# Pi_Servo_pHAT.net
KiCad netlist of a schematic drawn in EAGLE
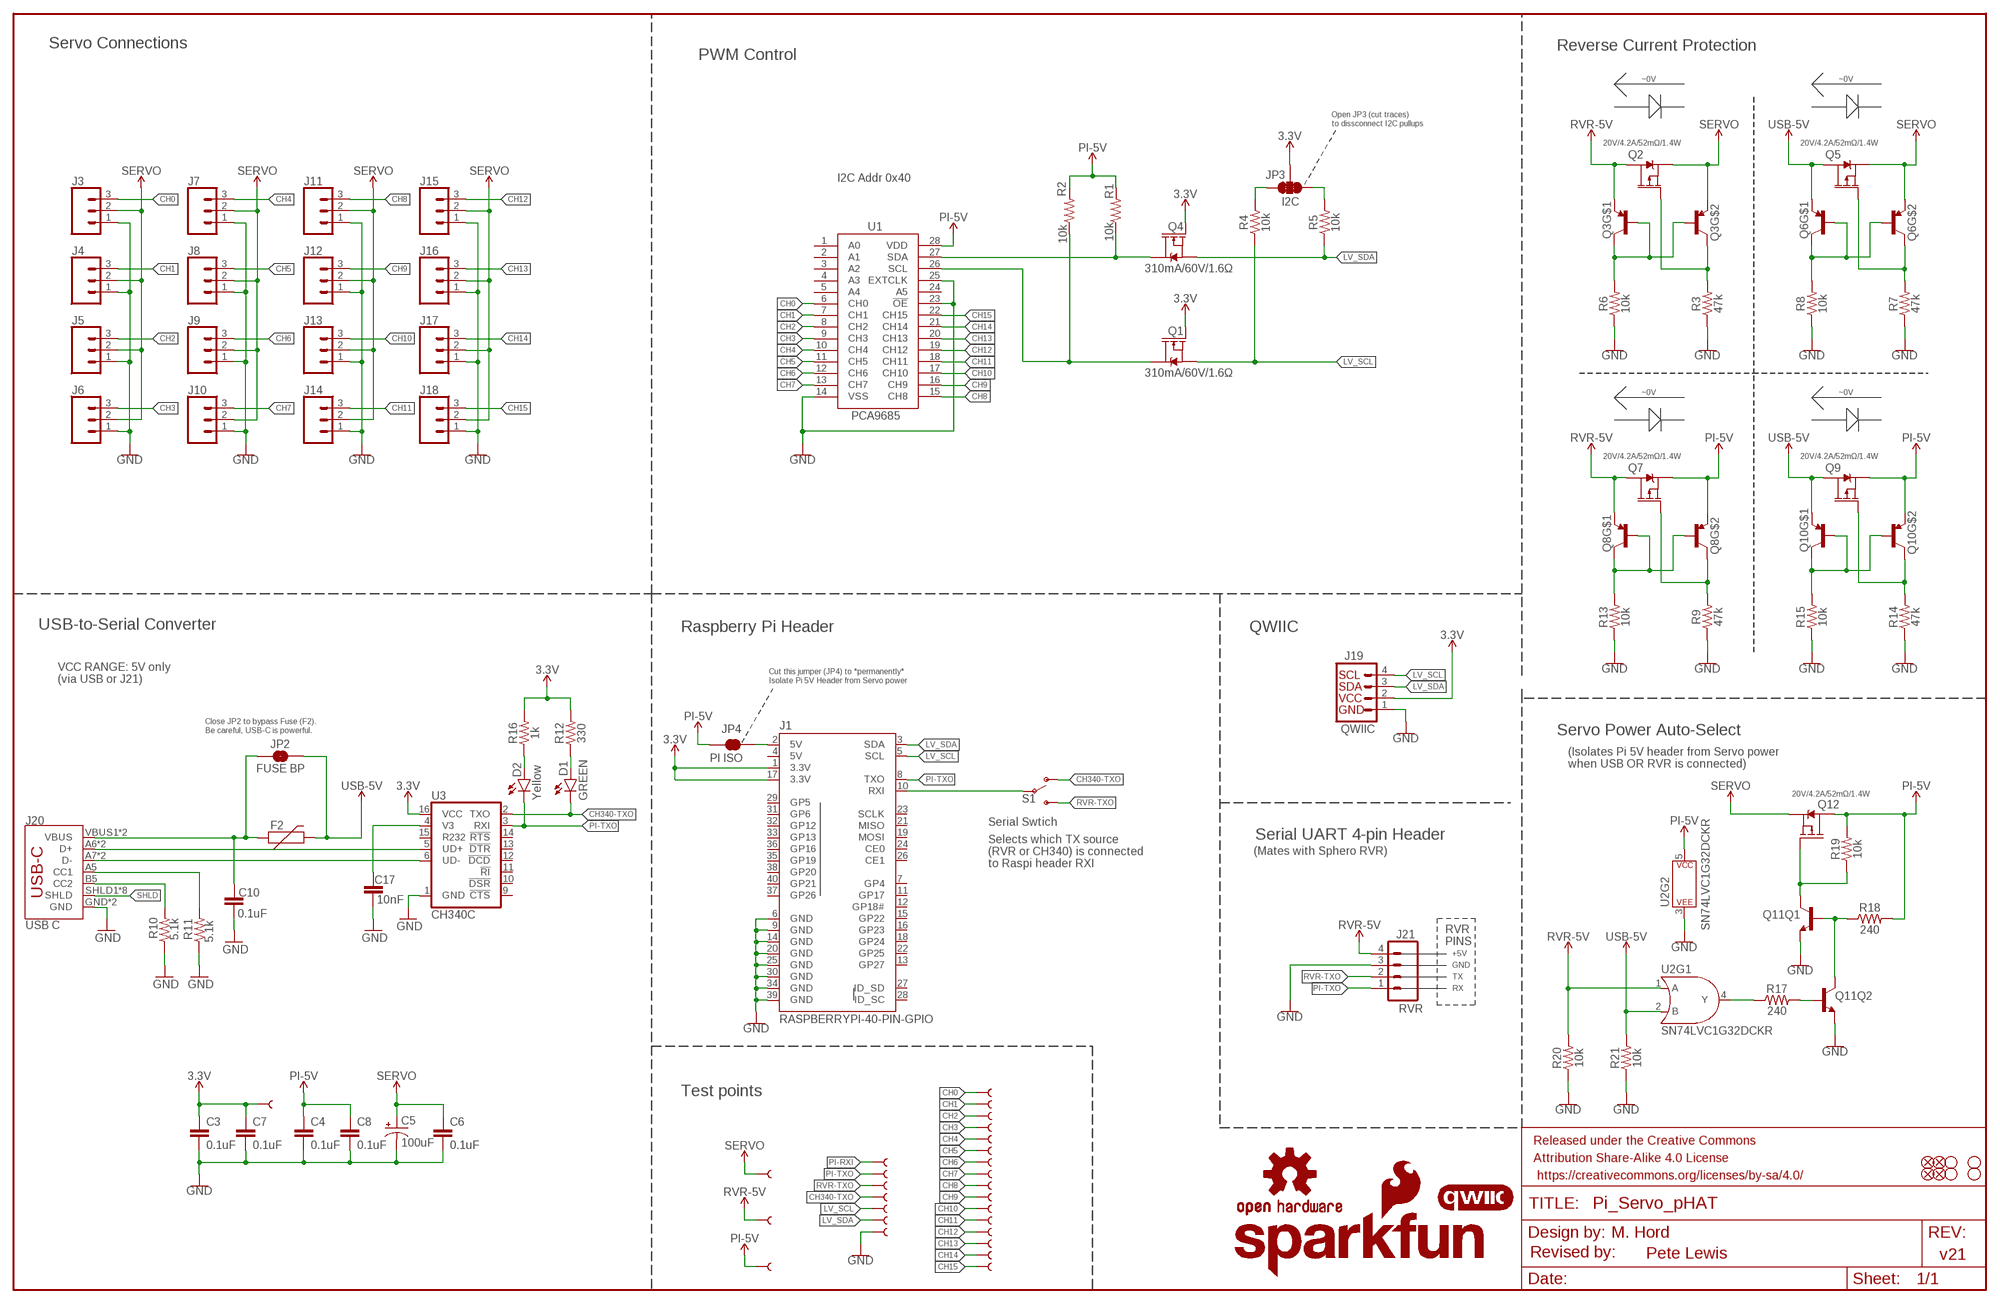
[diagram p0: schematic, sheet 1]

(export (version "E")
  (design (tool "Eeschema 10.0.6"))
  (components
    (comp (ref "C3")
      (value "0.1uF")
      (footprint "eagle-import:0603")
      (libsource (lib "eagle-import") (part "0.1UF-0603-25V-(+80/-20%)"))
    )
    (comp (ref "C4")
      (value "0.1uF")
      (footprint "eagle-import:0603")
      (libsource (lib "eagle-import") (part "0.1UF-0603-25V-(+80/-20%)"))
    )
    (comp (ref "C5")
      (value "100uF")
      (footprint "eagle-import:PANASONIC_D")
      (libsource (lib "eagle-import") (part "100UF-POLAR-25V-20%(ELEC)"))
    )
    (comp (ref "C6")
      (value "0.1uF")
      (footprint "eagle-import:0603")
      (libsource (lib "eagle-import") (part "0.1UF-0603-25V-(+80/-20%)"))
    )
    (comp (ref "C7")
      (value "0.1uF")
      (footprint "eagle-import:0603")
      (libsource (lib "eagle-import") (part "0.1UF-0603-25V-(+80/-20%)"))
    )
    (comp (ref "C8")
      (value "0.1uF")
      (footprint "eagle-import:0603")
      (libsource (lib "eagle-import") (part "0.1UF-0603-25V-(+80/-20%)"))
    )
    (comp (ref "C10")
      (value "0.1uF")
      (footprint "eagle-import:0603")
      (libsource (lib "eagle-import") (part "0.1UF-0603-25V-(+80/-20%)"))
    )
    (comp (ref "C17")
      (value "10nF")
      (footprint "eagle-import:0603")
      (libsource (lib "eagle-import") (part "10NF-0603-50V-10%"))
    )
    (comp (ref "D1")
      (value "GREEN")
      (footprint "eagle-import:LED-0603")
      (libsource (lib "eagle-import") (part "LED-GREEN0603"))
    )
    (comp (ref "D2")
      (value "Yellow")
      (footprint "eagle-import:LED-0603")
      (libsource (lib "eagle-import") (part "LED-YELLOW0603"))
    )
    (comp (ref "F2")
      (value "16V/2.5A(5A TRIP)")
      (footprint "eagle-import:1812")
      (libsource (lib "eagle-import") (part "PPTC_16V_2.5A"))
    )
    (comp (ref "FD1")
      (value "FIDUCIALUFIDUCIAL")
      (footprint "eagle-import:FIDUCIAL-MICRO")
      (libsource (lib "eagle-import") (part "FIDUCIALUFIDUCIAL"))
    )
    (comp (ref "FD2")
      (value "FIDUCIALUFIDUCIAL")
      (footprint "eagle-import:FIDUCIAL-MICRO")
      (libsource (lib "eagle-import") (part "FIDUCIALUFIDUCIAL"))
    )
    (comp (ref "FD3")
      (value "FIDUCIALUFIDUCIAL")
      (footprint "eagle-import:FIDUCIAL-MICRO")
      (libsource (lib "eagle-import") (part "FIDUCIALUFIDUCIAL"))
    )
    (comp (ref "FD4")
      (value "FIDUCIALUFIDUCIAL")
      (footprint "eagle-import:FIDUCIAL-MICRO")
      (libsource (lib "eagle-import") (part "FIDUCIALUFIDUCIAL"))
    )
    (comp (ref "FRAME2")
      (value "FRAME-LEDGER")
      (footprint "eagle-import:CREATIVE_COMMONS")
      (libsource (lib "eagle-import") (part "FRAME-LEDGER"))
    )
    (comp (ref "H1")
      (value "STAND-OFF")
      (footprint "eagle-import:STAND-OFF")
      (libsource (lib "eagle-import") (part "STAND-OFF"))
    )
    (comp (ref "H2")
      (value "STAND-OFF")
      (footprint "eagle-import:STAND-OFF")
      (libsource (lib "eagle-import") (part "STAND-OFF"))
    )
    (comp (ref "H3")
      (value "STAND-OFF")
      (footprint "eagle-import:STAND-OFF")
      (libsource (lib "eagle-import") (part "STAND-OFF"))
    )
    (comp (ref "H4")
      (value "STAND-OFF")
      (footprint "eagle-import:STAND-OFF")
      (libsource (lib "eagle-import") (part "STAND-OFF"))
    )
    (comp (ref "J1")
      (value "RASPBERRYPI-40-PIN-GPIO")
      (footprint "eagle-import:2X20")
      (libsource (lib "eagle-import") (part "RASPBERRYPI-40-PIN-GPIO_PTH_NO_SHROUD"))
    )
    (comp (ref "J3")
      (value "CONN_03")
      (footprint "eagle-import:1X03")
      (libsource (lib "eagle-import") (part "CONN_03"))
    )
    (comp (ref "J4")
      (value "CONN_03")
      (footprint "eagle-import:1X03")
      (libsource (lib "eagle-import") (part "CONN_03"))
    )
    (comp (ref "J5")
      (value "CONN_03")
      (footprint "eagle-import:1X03")
      (libsource (lib "eagle-import") (part "CONN_03"))
    )
    (comp (ref "J6")
      (value "CONN_03")
      (footprint "eagle-import:1X03")
      (libsource (lib "eagle-import") (part "CONN_03"))
    )
    (comp (ref "J7")
      (value "CONN_03")
      (footprint "eagle-import:1X03")
      (libsource (lib "eagle-import") (part "CONN_03"))
    )
    (comp (ref "J8")
      (value "CONN_03")
      (footprint "eagle-import:1X03")
      (libsource (lib "eagle-import") (part "CONN_03"))
    )
    (comp (ref "J9")
      (value "CONN_03")
      (footprint "eagle-import:1X03")
      (libsource (lib "eagle-import") (part "CONN_03"))
    )
    (comp (ref "J10")
      (value "CONN_03")
      (footprint "eagle-import:1X03")
      (libsource (lib "eagle-import") (part "CONN_03"))
    )
    (comp (ref "J11")
      (value "CONN_03")
      (footprint "eagle-import:1X03")
      (libsource (lib "eagle-import") (part "CONN_03"))
    )
    (comp (ref "J12")
      (value "CONN_03")
      (footprint "eagle-import:1X03")
      (libsource (lib "eagle-import") (part "CONN_03"))
    )
    (comp (ref "J13")
      (value "CONN_03")
      (footprint "eagle-import:1X03")
      (libsource (lib "eagle-import") (part "CONN_03"))
    )
    (comp (ref "J14")
      (value "CONN_03")
      (footprint "eagle-import:1X03")
      (libsource (lib "eagle-import") (part "CONN_03"))
    )
    (comp (ref "J15")
      (value "CONN_03")
      (footprint "eagle-import:1X03")
      (libsource (lib "eagle-import") (part "CONN_03"))
    )
    (comp (ref "J16")
      (value "CONN_03")
      (footprint "eagle-import:1X03")
      (libsource (lib "eagle-import") (part "CONN_03"))
    )
    (comp (ref "J17")
      (value "CONN_03")
      (footprint "eagle-import:1X03")
      (libsource (lib "eagle-import") (part "CONN_03"))
    )
    (comp (ref "J18")
      (value "CONN_03")
      (footprint "eagle-import:1X03")
      (libsource (lib "eagle-import") (part "CONN_03"))
    )
    (comp (ref "J19")
      (value "QWIIC")
      (footprint "eagle-import:JST04_1MM_RA")
      (libsource (lib "eagle-import") (part "QWIIC_CONNECTORJS-1MM"))
    )
    (comp (ref "J20")
      (value "USB C")
      (footprint "eagle-import:USB-C-16P")
      (libsource (lib "eagle-import") (part "USB_C16PIN"))
    )
    (comp (ref "J21")
      (value "RVR")
      (footprint "eagle-import:1X04_LOCK")
      (libsource (lib "eagle-import") (part "CONN_04LOCK"))
    )
    (comp (ref "JP2")
      (value "FUSE BP")
      (footprint "eagle-import:SMT-JUMPER_2_NO_SILK")
      (libsource (lib "eagle-import") (part "JUMPER-SMT_2_NO_SILK"))
    )
    (comp (ref "JP3")
      (value "I2C")
      (footprint "eagle-import:SMT-JUMPER_3_2-NC_TRACE_SILK")
      (libsource (lib "eagle-import") (part "JUMPER-SMT_3_2-NC_TRACE_SILK"))
    )
    (comp (ref "JP4")
      (value "PI ISO")
      (footprint "eagle-import:SMT-JUMPER_2_NC_TRACE_SILK")
      (libsource (lib "eagle-import") (part "JUMPER-SMT_2_NC_TRACE_SILK"))
    )
    (comp (ref "LOGO1")
      (value "SFE_LOGO_NAME_FLAME.1_INCH")
      (footprint "eagle-import:SFE_LOGO_NAME_FLAME_.1")
      (libsource (lib "eagle-import") (part "SFE_LOGO_NAME_FLAME.1_INCH"))
    )
    (comp (ref "LOGO2")
      (value "OSHW-LOGOS")
      (footprint "eagle-import:OSHW-LOGO-S")
      (libsource (lib "eagle-import") (part "OSHW-LOGOS"))
    )
    (comp (ref "Q1")
      (value "310mA/60V/1.6Ω")
      (footprint "eagle-import:SOT323")
      (libsource (lib "eagle-import") (part "MOSFET-NCH-2N7002PW"))
    )
    (comp (ref "Q2")
      (value "20V/4.2A/52mΩ/1.4W")
      (footprint "eagle-import:SOT23-3")
      (libsource (lib "eagle-import") (part "MOSFET_PCH-DMG2305UX-7"))
    )
    (comp (ref "Q3")
      (value "TRANS_PNP_DUALSOT-363")
      (footprint "eagle-import:SOT363_PHILIPS")
      (libsource (lib "eagle-import") (part "TRANS_PNP_DUALSOT-363"))
    )
    (comp (ref "Q4")
      (value "310mA/60V/1.6Ω")
      (footprint "eagle-import:SOT323")
      (libsource (lib "eagle-import") (part "MOSFET-NCH-2N7002PW"))
    )
    (comp (ref "Q5")
      (value "20V/4.2A/52mΩ/1.4W")
      (footprint "eagle-import:SOT23-3")
      (libsource (lib "eagle-import") (part "MOSFET_PCH-DMG2305UX-7"))
    )
    (comp (ref "Q6")
      (value "TRANS_PNP_DUALSOT-363")
      (footprint "eagle-import:SOT363_PHILIPS")
      (libsource (lib "eagle-import") (part "TRANS_PNP_DUALSOT-363"))
    )
    (comp (ref "Q7")
      (value "20V/4.2A/52mΩ/1.4W")
      (footprint "eagle-import:SOT23-3")
      (libsource (lib "eagle-import") (part "MOSFET_PCH-DMG2305UX-7"))
    )
    (comp (ref "Q8")
      (value "TRANS_PNP_DUALSOT-363")
      (footprint "eagle-import:SOT363_PHILIPS")
      (libsource (lib "eagle-import") (part "TRANS_PNP_DUALSOT-363"))
    )
    (comp (ref "Q9")
      (value "20V/4.2A/52mΩ/1.4W")
      (footprint "eagle-import:SOT23-3")
      (libsource (lib "eagle-import") (part "MOSFET_PCH-DMG2305UX-7"))
    )
    (comp (ref "Q10")
      (value "TRANS_PNP_DUALSOT-363")
      (footprint "eagle-import:SOT363_PHILIPS")
      (libsource (lib "eagle-import") (part "TRANS_PNP_DUALSOT-363"))
    )
    (comp (ref "Q11")
      (value "TRANS_NPN_DUAL-MBT3904DW1T1")
      (footprint "eagle-import:SC70-6")
      (libsource (lib "eagle-import") (part "TRANS_NPN_DUAL-MBT3904DW1T1"))
    )
    (comp (ref "Q12")
      (value "20V/4.2A/52mΩ/1.4W")
      (footprint "eagle-import:SOT23-3")
      (libsource (lib "eagle-import") (part "MOSFET_PCH-DMG2305UX-7"))
    )
    (comp (ref "R1")
      (value "10k")
      (footprint "eagle-import:0603")
      (libsource (lib "eagle-import") (part "10KOHM-0603-1/10W-1%"))
    )
    (comp (ref "R2")
      (value "10k")
      (footprint "eagle-import:0603")
      (libsource (lib "eagle-import") (part "10KOHM-0603-1/10W-1%"))
    )
    (comp (ref "R3")
      (value "47k")
      (footprint "eagle-import:0603")
      (libsource (lib "eagle-import") (part "47KOHM-0603-1/10W-1%"))
    )
    (comp (ref "R4")
      (value "10k")
      (footprint "eagle-import:0603")
      (libsource (lib "eagle-import") (part "10KOHM-0603-1/10W-1%"))
    )
    (comp (ref "R5")
      (value "10k")
      (footprint "eagle-import:0603")
      (libsource (lib "eagle-import") (part "10KOHM-0603-1/10W-1%"))
    )
    (comp (ref "R6")
      (value "10k")
      (footprint "eagle-import:0603")
      (libsource (lib "eagle-import") (part "10KOHM-0603-1/10W-1%"))
    )
    (comp (ref "R7")
      (value "47k")
      (footprint "eagle-import:0603")
      (libsource (lib "eagle-import") (part "47KOHM-0603-1/10W-1%"))
    )
    (comp (ref "R8")
      (value "10k")
      (footprint "eagle-import:0603")
      (libsource (lib "eagle-import") (part "10KOHM-0603-1/10W-1%"))
    )
    (comp (ref "R9")
      (value "47k")
      (footprint "eagle-import:0603")
      (libsource (lib "eagle-import") (part "47KOHM-0603-1/10W-1%"))
    )
    (comp (ref "R10")
      (value "5.1k")
      (footprint "eagle-import:0603")
      (libsource (lib "eagle-import") (part "5.1KOHM5.1KOHM-0603-1/10W-1%"))
    )
    (comp (ref "R11")
      (value "5.1k")
      (footprint "eagle-import:0603")
      (libsource (lib "eagle-import") (part "5.1KOHM5.1KOHM-0603-1/10W-1%"))
    )
    (comp (ref "R12")
      (value "330")
      (footprint "eagle-import:0603")
      (libsource (lib "eagle-import") (part "330OHM-0603-1/10W-1%"))
    )
    (comp (ref "R13")
      (value "10k")
      (footprint "eagle-import:0603")
      (libsource (lib "eagle-import") (part "10KOHM-0603-1/10W-1%"))
    )
    (comp (ref "R14")
      (value "47k")
      (footprint "eagle-import:0603")
      (libsource (lib "eagle-import") (part "47KOHM-0603-1/10W-1%"))
    )
    (comp (ref "R15")
      (value "10k")
      (footprint "eagle-import:0603")
      (libsource (lib "eagle-import") (part "10KOHM-0603-1/10W-1%"))
    )
    (comp (ref "R16")
      (value "1k")
      (footprint "eagle-import:0603")
      (libsource (lib "eagle-import") (part "1KOHM-0603-1/10W-1%"))
    )
    (comp (ref "R17")
      (value "240")
      (footprint "eagle-import:0603")
      (libsource (lib "eagle-import") (part "240OHM-0603-1/10W-1%"))
    )
    (comp (ref "R18")
      (value "240")
      (footprint "eagle-import:0603")
      (libsource (lib "eagle-import") (part "240OHM-0603-1/10W-1%"))
    )
    (comp (ref "R19")
      (value "10k")
      (footprint "eagle-import:0603")
      (libsource (lib "eagle-import") (part "10KOHM-0603-1/10W-1%"))
    )
    (comp (ref "R20")
      (value "10k")
      (footprint "eagle-import:0603")
      (libsource (lib "eagle-import") (part "10KOHM-0603-1/10W-1%"))
    )
    (comp (ref "R21")
      (value "10k")
      (footprint "eagle-import:0603")
      (libsource (lib "eagle-import") (part "10KOHM-0603-1/10W-1%"))
    )
    (comp (ref "S1")
      (value "SWITCH-SPDT-SMD-RIGHT-ANGLE")
      (footprint "eagle-import:SWITCH_SPST_SMD_A")
      (libsource (lib "eagle-import") (part "SWITCH-SPDT-SMD-RIGHT-ANGLE"))
    )
    (comp (ref "TP0")
      (value "TEST-POINT3X4")
      (footprint "eagle-import:PAD.03X.04")
      (libsource (lib "eagle-import") (part "TEST-POINT3X4"))
    )
    (comp (ref "TP1")
      (value "TEST-POINT3X4")
      (footprint "eagle-import:PAD.03X.04")
      (libsource (lib "eagle-import") (part "TEST-POINT3X4"))
    )
    (comp (ref "TP2")
      (value "TEST-POINT3X4")
      (footprint "eagle-import:PAD.03X.04")
      (libsource (lib "eagle-import") (part "TEST-POINT3X4"))
    )
    (comp (ref "TP3")
      (value "TEST-POINT3X4")
      (footprint "eagle-import:PAD.03X.04")
      (libsource (lib "eagle-import") (part "TEST-POINT3X4"))
    )
    (comp (ref "TP4")
      (value "TEST-POINT3X4")
      (footprint "eagle-import:PAD.03X.04")
      (libsource (lib "eagle-import") (part "TEST-POINT3X4"))
    )
    (comp (ref "TP5")
      (value "TEST-POINT3X4")
      (footprint "eagle-import:PAD.03X.04")
      (libsource (lib "eagle-import") (part "TEST-POINT3X4"))
    )
    (comp (ref "TP6")
      (value "TEST-POINT3X4")
      (footprint "eagle-import:PAD.03X.04")
      (libsource (lib "eagle-import") (part "TEST-POINT3X4"))
    )
    (comp (ref "TP7")
      (value "TEST-POINT3X4")
      (footprint "eagle-import:PAD.03X.04")
      (libsource (lib "eagle-import") (part "TEST-POINT3X4"))
    )
    (comp (ref "TP8")
      (value "TEST-POINT3X4")
      (footprint "eagle-import:PAD.03X.04")
      (libsource (lib "eagle-import") (part "TEST-POINT3X4"))
    )
    (comp (ref "TP9")
      (value "TEST-POINT3X4")
      (footprint "eagle-import:PAD.03X.04")
      (libsource (lib "eagle-import") (part "TEST-POINT3X4"))
    )
    (comp (ref "TP10")
      (value "TEST-POINT3X4")
      (footprint "eagle-import:PAD.03X.04")
      (libsource (lib "eagle-import") (part "TEST-POINT3X4"))
    )
    (comp (ref "TP11")
      (value "TEST-POINT3X4")
      (footprint "eagle-import:PAD.03X.04")
      (libsource (lib "eagle-import") (part "TEST-POINT3X4"))
    )
    (comp (ref "TP12")
      (value "TEST-POINT3X4")
      (footprint "eagle-import:PAD.03X.04")
      (libsource (lib "eagle-import") (part "TEST-POINT3X4"))
    )
    (comp (ref "TP13")
      (value "TEST-POINT3X4")
      (footprint "eagle-import:PAD.03X.04")
      (libsource (lib "eagle-import") (part "TEST-POINT3X4"))
    )
    (comp (ref "TP14")
      (value "TEST-POINT3X4")
      (footprint "eagle-import:PAD.03X.04")
      (libsource (lib "eagle-import") (part "TEST-POINT3X4"))
    )
    (comp (ref "TP15")
      (value "TEST-POINT3X4")
      (footprint "eagle-import:PAD.03X.04")
      (libsource (lib "eagle-import") (part "TEST-POINT3X4"))
    )
    (comp (ref "TP16")
      (value "TEST-POINT3X4")
      (footprint "eagle-import:PAD.03X.04")
      (libsource (lib "eagle-import") (part "TEST-POINT3X4"))
    )
    (comp (ref "TP17")
      (value "TEST-POINT3X4")
      (footprint "eagle-import:PAD.03X.04")
      (libsource (lib "eagle-import") (part "TEST-POINT3X4"))
    )
    (comp (ref "TP18")
      (value "TEST-POINTTP_15TH_THRU")
      (footprint "eagle-import:TP_15TH")
      (libsource (lib "eagle-import") (part "TEST-POINTTP_15TH_THRU"))
    )
    (comp (ref "TP19")
      (value "TEST-POINTTP_15TH_THRU")
      (footprint "eagle-import:TP_15TH")
      (libsource (lib "eagle-import") (part "TEST-POINTTP_15TH_THRU"))
    )
    (comp (ref "TP20")
      (value "TEST-POINT3X4")
      (footprint "eagle-import:PAD.03X.04")
      (libsource (lib "eagle-import") (part "TEST-POINT3X4"))
    )
    (comp (ref "TP21")
      (value "TEST-POINT3X4")
      (footprint "eagle-import:PAD.03X.04")
      (libsource (lib "eagle-import") (part "TEST-POINT3X4"))
    )
    (comp (ref "TP22")
      (value "TEST-POINT3X4")
      (footprint "eagle-import:PAD.03X.04")
      (libsource (lib "eagle-import") (part "TEST-POINT3X4"))
    )
    (comp (ref "TP23")
      (value "TEST-POINT3X4")
      (footprint "eagle-import:PAD.03X.04")
      (libsource (lib "eagle-import") (part "TEST-POINT3X4"))
    )
    (comp (ref "TP24")
      (value "TEST-POINT3X4")
      (footprint "eagle-import:PAD.03X.04")
      (libsource (lib "eagle-import") (part "TEST-POINT3X4"))
    )
    (comp (ref "TP25")
      (value "TEST-POINT3X4")
      (footprint "eagle-import:PAD.03X.04")
      (libsource (lib "eagle-import") (part "TEST-POINT3X4"))
    )
    (comp (ref "TP26")
      (value "TEST-POINT3X4")
      (footprint "eagle-import:PAD.03X.04")
      (libsource (lib "eagle-import") (part "TEST-POINT3X4"))
    )
    (comp (ref "U$1")
      (value "QWIIC_LOGO_5MM")
      (footprint "eagle-import:QWIIC_5MM")
      (libsource (lib "eagle-import") (part "QWIIC_LOGO_5MM"))
    )
    (comp (ref "U1")
      (value "PCA9685")
      (footprint "eagle-import:TSSOP-28_4MM")
      (libsource (lib "eagle-import") (part "PCA9685"))
    )
    (comp (ref "U2")
      (value "SN74LVC1G32DCKR")
      (footprint "eagle-import:SOT353")
      (libsource (lib "eagle-import") (part "7432"))
    )
    (comp (ref "U3")
      (value "CH340C")
      (footprint "eagle-import:SO016")
      (libsource (lib "eagle-import") (part "CH340C"))
    )
  )
  (nets
    (net (code "1") (name "/5V") (class "Default")
      (node (ref "J1") (pin "4") (pinfunction "5V_4") (pintype "power_in"))
    )
    (net (code "2") (name "3.3V") (class "Default")
      (node (ref "C3") (pin "1") (pinfunction "1_1") (pintype "passive"))
      (node (ref "C7") (pin "1") (pinfunction "1_1") (pintype "passive"))
      (node (ref "J1") (pin "1") (pinfunction "3.3V_1") (pintype "power_in"))
      (node (ref "J1") (pin "17") (pinfunction "3.3V_17") (pintype "power_in"))
      (node (ref "J19") (pin "2") (pinfunction "2_2") (pintype "power_in"))
      (node (ref "JP3") (pin "2") (pinfunction "2_2") (pintype "passive"))
      (node (ref "Q1") (pin "1") (pinfunction "G_1") (pintype "bidirectional"))
      (node (ref "Q4") (pin "1") (pinfunction "G_1") (pintype "bidirectional"))
      (node (ref "R12") (pin "2") (pinfunction "2_2") (pintype "passive"))
      (node (ref "R16") (pin "2") (pinfunction "2_2") (pintype "passive"))
      (node (ref "TP22") (pin "P$1") (pinfunction "1_P$1") (pintype "bidirectional"))
      (node (ref "U3") (pin "16") (pinfunction "VCC_16") (pintype "bidirectional"))
    )
    (net (code "3") (name "CH0") (class "Default")
      (node (ref "J3") (pin "3") (pinfunction "3_3") (pintype "passive"))
      (node (ref "TP0") (pin "P$1") (pinfunction "1_P$1") (pintype "bidirectional"))
      (node (ref "U1") (pin "6") (pinfunction "CH0_6") (pintype "bidirectional"))
    )
    (net (code "4") (name "CH1") (class "Default")
      (node (ref "J4") (pin "3") (pinfunction "3_3") (pintype "passive"))
      (node (ref "TP1") (pin "P$1") (pinfunction "1_P$1") (pintype "bidirectional"))
      (node (ref "U1") (pin "7") (pinfunction "CH1_7") (pintype "bidirectional"))
    )
    (net (code "5") (name "CH2") (class "Default")
      (node (ref "J5") (pin "3") (pinfunction "3_3") (pintype "passive"))
      (node (ref "TP2") (pin "P$1") (pinfunction "1_P$1") (pintype "bidirectional"))
      (node (ref "U1") (pin "8") (pinfunction "CH2_8") (pintype "bidirectional"))
    )
    (net (code "6") (name "CH3") (class "Default")
      (node (ref "J6") (pin "3") (pinfunction "3_3") (pintype "passive"))
      (node (ref "TP3") (pin "P$1") (pinfunction "1_P$1") (pintype "bidirectional"))
      (node (ref "U1") (pin "9") (pinfunction "CH3_9") (pintype "bidirectional"))
    )
    (net (code "7") (name "CH4") (class "Default")
      (node (ref "J7") (pin "3") (pinfunction "3_3") (pintype "passive"))
      (node (ref "TP4") (pin "P$1") (pinfunction "1_P$1") (pintype "bidirectional"))
      (node (ref "U1") (pin "10") (pinfunction "CH4_10") (pintype "bidirectional"))
    )
    (net (code "8") (name "CH5") (class "Default")
      (node (ref "J8") (pin "3") (pinfunction "3_3") (pintype "passive"))
      (node (ref "TP5") (pin "P$1") (pinfunction "1_P$1") (pintype "bidirectional"))
      (node (ref "U1") (pin "11") (pinfunction "CH5_11") (pintype "bidirectional"))
    )
    (net (code "9") (name "CH6") (class "Default")
      (node (ref "J9") (pin "3") (pinfunction "3_3") (pintype "passive"))
      (node (ref "TP6") (pin "P$1") (pinfunction "1_P$1") (pintype "bidirectional"))
      (node (ref "U1") (pin "12") (pinfunction "CH6_12") (pintype "bidirectional"))
    )
    (net (code "10") (name "CH7") (class "Default")
      (node (ref "J10") (pin "3") (pinfunction "3_3") (pintype "passive"))
      (node (ref "TP7") (pin "P$1") (pinfunction "1_P$1") (pintype "bidirectional"))
      (node (ref "U1") (pin "13") (pinfunction "CH7_13") (pintype "bidirectional"))
    )
    (net (code "11") (name "CH8") (class "Default")
      (node (ref "J11") (pin "3") (pinfunction "3_3") (pintype "passive"))
      (node (ref "TP8") (pin "P$1") (pinfunction "1_P$1") (pintype "bidirectional"))
      (node (ref "U1") (pin "15") (pinfunction "CH8_15") (pintype "bidirectional"))
    )
    (net (code "12") (name "CH9") (class "Default")
      (node (ref "J12") (pin "3") (pinfunction "3_3") (pintype "passive"))
      (node (ref "TP9") (pin "P$1") (pinfunction "1_P$1") (pintype "bidirectional"))
      (node (ref "U1") (pin "16") (pinfunction "CH9_16") (pintype "bidirectional"))
    )
    (net (code "13") (name "CH10") (class "Default")
      (node (ref "J13") (pin "3") (pinfunction "3_3") (pintype "passive"))
      (node (ref "TP10") (pin "P$1") (pinfunction "1_P$1") (pintype "bidirectional"))
      (node (ref "U1") (pin "17") (pinfunction "CH10_17") (pintype "bidirectional"))
    )
    (net (code "14") (name "CH11") (class "Default")
      (node (ref "J14") (pin "3") (pinfunction "3_3") (pintype "passive"))
      (node (ref "TP11") (pin "P$1") (pinfunction "1_P$1") (pintype "bidirectional"))
      (node (ref "U1") (pin "18") (pinfunction "CH11_18") (pintype "bidirectional"))
    )
    (net (code "15") (name "CH12") (class "Default")
      (node (ref "J15") (pin "3") (pinfunction "3_3") (pintype "passive"))
      (node (ref "TP12") (pin "P$1") (pinfunction "1_P$1") (pintype "bidirectional"))
      (node (ref "U1") (pin "19") (pinfunction "CH12_19") (pintype "bidirectional"))
    )
    (net (code "16") (name "CH13") (class "Default")
      (node (ref "J16") (pin "3") (pinfunction "3_3") (pintype "passive"))
      (node (ref "TP13") (pin "P$1") (pinfunction "1_P$1") (pintype "bidirectional"))
      (node (ref "U1") (pin "20") (pinfunction "CH13_20") (pintype "bidirectional"))
    )
    (net (code "17") (name "CH14") (class "Default")
      (node (ref "J17") (pin "3") (pinfunction "3_3") (pintype "passive"))
      (node (ref "TP14") (pin "P$1") (pinfunction "1_P$1") (pintype "bidirectional"))
      (node (ref "U1") (pin "21") (pinfunction "CH14_21") (pintype "bidirectional"))
    )
    (net (code "18") (name "CH15") (class "Default")
      (node (ref "J18") (pin "3") (pinfunction "3_3") (pintype "passive"))
      (node (ref "TP15") (pin "P$1") (pinfunction "1_P$1") (pintype "bidirectional"))
      (node (ref "U1") (pin "22") (pinfunction "CH15_22") (pintype "bidirectional"))
    )
    (net (code "19") (name "CH340-TXO") (class "Default")
      (node (ref "D1") (pin "C") (pinfunction "C_C") (pintype "passive"))
      (node (ref "S1") (pin "1") (pinfunction "O_1") (pintype "passive"))
      (node (ref "TP23") (pin "P$1") (pinfunction "1_P$1") (pintype "bidirectional"))
      (node (ref "U3") (pin "2") (pinfunction "TXO_2") (pintype "bidirectional"))
    )
    (net (code "20") (name "GND") (class "Default")
      (node (ref "C10") (pin "2") (pinfunction "2_2") (pintype "passive"))
      (node (ref "C17") (pin "2") (pinfunction "2_2") (pintype "passive"))
      (node (ref "C3") (pin "2") (pinfunction "2_2") (pintype "passive"))
      (node (ref "C4") (pin "2") (pinfunction "2_2") (pintype "passive"))
      (node (ref "C5") (pin "-") (pinfunction "-_-") (pintype "passive"))
      (node (ref "C6") (pin "2") (pinfunction "2_2") (pintype "passive"))
      (node (ref "C7") (pin "2") (pinfunction "2_2") (pintype "passive"))
      (node (ref "C8") (pin "2") (pinfunction "2_2") (pintype "passive"))
      (node (ref "J1") (pin "14") (pinfunction "GND_14") (pintype "power_in"))
      (node (ref "J1") (pin "20") (pinfunction "GND_20") (pintype "power_in"))
      (node (ref "J1") (pin "25") (pinfunction "GND_25") (pintype "power_in"))
      (node (ref "J1") (pin "30") (pinfunction "GND_30") (pintype "power_in"))
      (node (ref "J1") (pin "34") (pinfunction "GND_34") (pintype "power_in"))
      (node (ref "J1") (pin "39") (pinfunction "GND_39") (pintype "power_in"))
      (node (ref "J1") (pin "6") (pinfunction "GND_6") (pintype "power_in"))
      (node (ref "J1") (pin "9") (pinfunction "GND_9") (pintype "power_in"))
      (node (ref "J10") (pin "1") (pinfunction "1_1") (pintype "passive"))
      (node (ref "J11") (pin "1") (pinfunction "1_1") (pintype "passive"))
      (node (ref "J12") (pin "1") (pinfunction "1_1") (pintype "passive"))
      (node (ref "J13") (pin "1") (pinfunction "1_1") (pintype "passive"))
      (node (ref "J14") (pin "1") (pinfunction "1_1") (pintype "passive"))
      (node (ref "J15") (pin "1") (pinfunction "1_1") (pintype "passive"))
      (node (ref "J16") (pin "1") (pinfunction "1_1") (pintype "passive"))
      (node (ref "J17") (pin "1") (pinfunction "1_1") (pintype "passive"))
      (node (ref "J18") (pin "1") (pinfunction "1_1") (pintype "passive"))
      (node (ref "J19") (pin "1") (pinfunction "1_1") (pintype "power_in"))
      (node (ref "J20") (pin "GND") (pinfunction "GND_GND") (pintype "bidirectional"))
      (node (ref "J20") (pin "GND2") (pinfunction "GND_GND2") (pintype "bidirectional"))
      (node (ref "J21") (pin "3") (pinfunction "3_3") (pintype "passive"))
      (node (ref "J3") (pin "1") (pinfunction "1_1") (pintype "passive"))
      (node (ref "J4") (pin "1") (pinfunction "1_1") (pintype "passive"))
      (node (ref "J5") (pin "1") (pinfunction "1_1") (pintype "passive"))
      (node (ref "J6") (pin "1") (pinfunction "1_1") (pintype "passive"))
      (node (ref "J7") (pin "1") (pinfunction "1_1") (pintype "passive"))
      (node (ref "J8") (pin "1") (pinfunction "1_1") (pintype "passive"))
      (node (ref "J9") (pin "1") (pinfunction "1_1") (pintype "passive"))
      (node (ref "Q11") (pin "1") (pinfunction "E_1") (pintype "passive"))
      (node (ref "Q11") (pin "4") (pinfunction "E_4") (pintype "passive"))
      (node (ref "R10") (pin "1") (pinfunction "1_1") (pintype "passive"))
      (node (ref "R11") (pin "1") (pinfunction "1_1") (pintype "passive"))
      (node (ref "R13") (pin "1") (pinfunction "1_1") (pintype "passive"))
      (node (ref "R14") (pin "1") (pinfunction "1_1") (pintype "passive"))
      (node (ref "R15") (pin "1") (pinfunction "1_1") (pintype "passive"))
      (node (ref "R20") (pin "1") (pinfunction "1_1") (pintype "passive"))
      (node (ref "R21") (pin "1") (pinfunction "1_1") (pintype "passive"))
      (node (ref "R3") (pin "1") (pinfunction "1_1") (pintype "passive"))
      (node (ref "R6") (pin "1") (pinfunction "1_1") (pintype "passive"))
      (node (ref "R7") (pin "1") (pinfunction "1_1") (pintype "passive"))
      (node (ref "R8") (pin "1") (pinfunction "1_1") (pintype "passive"))
      (node (ref "R9") (pin "1") (pinfunction "1_1") (pintype "passive"))
      (node (ref "TP17") (pin "P$1") (pinfunction "1_P$1") (pintype "bidirectional"))
      (node (ref "U1") (pin "14") (pinfunction "VSS_14") (pintype "bidirectional"))
      (node (ref "U1") (pin "23") (pinfunction "~{OE}_23") (pintype "bidirectional"))
      (node (ref "U1") (pin "25") (pinfunction "EXTCLK_25") (pintype "bidirectional"))
      (node (ref "U2") (pin "3") (pinfunction "P$V-_3") (pintype "bidirectional"))
      (node (ref "U3") (pin "1") (pinfunction "GND_1") (pintype "bidirectional"))
    )
    (net (code "21") (name "LV_SCL") (class "Default")
      (node (ref "J1") (pin "5") (pinfunction "SCL_5") (pintype "bidirectional"))
      (node (ref "J19") (pin "4") (pinfunction "4_4") (pintype "passive"))
      (node (ref "Q1") (pin "2") (pinfunction "S_2") (pintype "bidirectional"))
      (node (ref "R4") (pin "1") (pinfunction "1_1") (pintype "passive"))
      (node (ref "TP18") (pin "P$1") (pinfunction "1_P$1") (pintype "bidirectional"))
    )
    (net (code "22") (name "LV_SDA") (class "Default")
      (node (ref "J1") (pin "3") (pinfunction "SDA_3") (pintype "bidirectional"))
      (node (ref "J19") (pin "3") (pinfunction "3_3") (pintype "passive"))
      (node (ref "Q4") (pin "2") (pinfunction "S_2") (pintype "bidirectional"))
      (node (ref "R5") (pin "1") (pinfunction "1_1") (pintype "passive"))
      (node (ref "TP19") (pin "P$1") (pinfunction "1_P$1") (pintype "bidirectional"))
    )
    (net (code "23") (name "Net-(C10-Pad1)") (class "Default")
      (node (ref "C10") (pin "1") (pinfunction "1_1") (pintype "passive"))
      (node (ref "F2") (pin "1") (pinfunction "1_1") (pintype "bidirectional"))
      (node (ref "J20") (pin "VBUS1") (pinfunction "VBUS_VBUS1") (pintype "bidirectional"))
      (node (ref "J20") (pin "VBUS2") (pinfunction "VBUS_VBUS2") (pintype "bidirectional"))
      (node (ref "JP2") (pin "1") (pinfunction "1_1") (pintype "passive"))
    )
    (net (code "24") (name "Net-(D1-PadA)") (class "Default")
      (node (ref "D1") (pin "A") (pinfunction "A_A") (pintype "passive"))
      (node (ref "R12") (pin "1") (pinfunction "1_1") (pintype "passive"))
    )
    (net (code "25") (name "Net-(D2-PadA)") (class "Default")
      (node (ref "D2") (pin "A") (pinfunction "A_A") (pintype "passive"))
      (node (ref "R16") (pin "1") (pinfunction "1_1") (pintype "passive"))
    )
    (net (code "26") (name "Net-(J1-5V-Pad2)") (class "Default")
      (node (ref "J1") (pin "2") (pinfunction "5V_2") (pintype "power_in"))
      (node (ref "JP4") (pin "2") (pinfunction "2_2") (pintype "passive"))
    )
    (net (code "27") (name "Net-(J20-CC1)") (class "Default")
      (node (ref "J20") (pin "A5") (pinfunction "CC1_A5") (pintype "bidirectional"))
      (node (ref "R11") (pin "2") (pinfunction "2_2") (pintype "passive"))
    )
    (net (code "28") (name "Net-(J20-CC2)") (class "Default")
      (node (ref "J20") (pin "B5") (pinfunction "CC2_B5") (pintype "bidirectional"))
      (node (ref "R10") (pin "2") (pinfunction "2_2") (pintype "passive"))
    )
    (net (code "29") (name "Net-(JP3-Pad1)") (class "Default")
      (node (ref "JP3") (pin "1") (pinfunction "1_1") (pintype "passive"))
      (node (ref "R5") (pin "2") (pinfunction "2_2") (pintype "passive"))
    )
    (net (code "30") (name "Net-(JP3-Pad3)") (class "Default")
      (node (ref "JP3") (pin "3") (pinfunction "3_3") (pintype "passive"))
      (node (ref "R4") (pin "2") (pinfunction "2_2") (pintype "passive"))
    )
    (net (code "31") (name "Net-(Q1-D)") (class "Default")
      (node (ref "Q1") (pin "3") (pinfunction "D_3") (pintype "bidirectional"))
      (node (ref "R2") (pin "1") (pinfunction "1_1") (pintype "passive"))
      (node (ref "U1") (pin "26") (pinfunction "SCL_26") (pintype "bidirectional"))
    )
    (net (code "32") (name "Net-(Q2-G)") (class "Default")
      (node (ref "Q2") (pin "1") (pinfunction "G_1") (pintype "bidirectional"))
      (node (ref "Q3") (pin "3") (pinfunction "C_3") (pintype "passive"))
      (node (ref "R3") (pin "2") (pinfunction "2_2") (pintype "passive"))
    )
    (net (code "33") (name "Net-(Q3A-B)") (class "Default")
      (node (ref "Q3") (pin "2") (pinfunction "B_2") (pintype "passive"))
      (node (ref "Q3") (pin "5") (pinfunction "B_5") (pintype "passive"))
      (node (ref "Q3") (pin "6") (pinfunction "C_6") (pintype "passive"))
      (node (ref "R6") (pin "2") (pinfunction "2_2") (pintype "passive"))
    )
    (net (code "34") (name "Net-(Q4-D)") (class "Default")
      (node (ref "Q4") (pin "3") (pinfunction "D_3") (pintype "bidirectional"))
      (node (ref "R1") (pin "1") (pinfunction "1_1") (pintype "passive"))
      (node (ref "U1") (pin "27") (pinfunction "SDA_27") (pintype "bidirectional"))
    )
    (net (code "35") (name "Net-(Q5-G)") (class "Default")
      (node (ref "Q5") (pin "1") (pinfunction "G_1") (pintype "bidirectional"))
      (node (ref "Q6") (pin "3") (pinfunction "C_3") (pintype "passive"))
      (node (ref "R7") (pin "2") (pinfunction "2_2") (pintype "passive"))
    )
    (net (code "36") (name "Net-(Q6A-B)") (class "Default")
      (node (ref "Q6") (pin "2") (pinfunction "B_2") (pintype "passive"))
      (node (ref "Q6") (pin "5") (pinfunction "B_5") (pintype "passive"))
      (node (ref "Q6") (pin "6") (pinfunction "C_6") (pintype "passive"))
      (node (ref "R8") (pin "2") (pinfunction "2_2") (pintype "passive"))
    )
    (net (code "37") (name "Net-(Q7-G)") (class "Default")
      (node (ref "Q7") (pin "1") (pinfunction "G_1") (pintype "bidirectional"))
      (node (ref "Q8") (pin "3") (pinfunction "C_3") (pintype "passive"))
      (node (ref "R9") (pin "2") (pinfunction "2_2") (pintype "passive"))
    )
    (net (code "38") (name "Net-(Q8A-B)") (class "Default")
      (node (ref "Q8") (pin "2") (pinfunction "B_2") (pintype "passive"))
      (node (ref "Q8") (pin "5") (pinfunction "B_5") (pintype "passive"))
      (node (ref "Q8") (pin "6") (pinfunction "C_6") (pintype "passive"))
      (node (ref "R13") (pin "2") (pinfunction "2_2") (pintype "passive"))
    )
    (net (code "39") (name "Net-(Q10A-B)") (class "Default")
      (node (ref "Q10") (pin "2") (pinfunction "B_2") (pintype "passive"))
      (node (ref "Q10") (pin "5") (pinfunction "B_5") (pintype "passive"))
      (node (ref "Q10") (pin "6") (pinfunction "C_6") (pintype "passive"))
      (node (ref "R15") (pin "2") (pinfunction "2_2") (pintype "passive"))
    )
    (net (code "40") (name "Net-(Q10B-C)") (class "Default")
      (node (ref "Q10") (pin "3") (pinfunction "C_3") (pintype "passive"))
      (node (ref "Q9") (pin "1") (pinfunction "G_1") (pintype "bidirectional"))
      (node (ref "R14") (pin "2") (pinfunction "2_2") (pintype "passive"))
    )
    (net (code "41") (name "Net-(Q11A-B)") (class "Default")
      (node (ref "Q11") (pin "5") (pinfunction "B_5") (pintype "passive"))
      (node (ref "Q11") (pin "6") (pinfunction "C_6") (pintype "passive"))
      (node (ref "R18") (pin "1") (pinfunction "1_1") (pintype "passive"))
    )
    (net (code "42") (name "Net-(Q11A-C)") (class "Default")
      (node (ref "Q11") (pin "3") (pinfunction "C_3") (pintype "passive"))
      (node (ref "Q12") (pin "1") (pinfunction "G_1") (pintype "bidirectional"))
      (node (ref "R19") (pin "1") (pinfunction "1_1") (pintype "passive"))
    )
    (net (code "43") (name "Net-(Q11B-B)") (class "Default")
      (node (ref "Q11") (pin "2") (pinfunction "B_2") (pintype "passive"))
      (node (ref "R17") (pin "2") (pinfunction "2_2") (pintype "passive"))
    )
    (net (code "44") (name "Net-(U2A-Y)") (class "Default")
      (node (ref "R17") (pin "1") (pinfunction "1_1") (pintype "passive"))
      (node (ref "U2") (pin "4") (pinfunction "Y_4") (pintype "bidirectional"))
    )
    (net (code "45") (name "Net-(U3-UD+)") (class "Default")
      (node (ref "J20") (pin "A6") (pinfunction "D+_A6") (pintype "bidirectional"))
      (node (ref "J20") (pin "B6") (pinfunction "D+_B6") (pintype "bidirectional"))
      (node (ref "U3") (pin "5") (pinfunction "UD+_5") (pintype "bidirectional"))
    )
    (net (code "46") (name "Net-(U3-UD-)") (class "Default")
      (node (ref "J20") (pin "A7") (pinfunction "D-_A7") (pintype "bidirectional"))
      (node (ref "J20") (pin "B7") (pinfunction "D-_B7") (pintype "bidirectional"))
      (node (ref "U3") (pin "6") (pinfunction "UD-_6") (pintype "bidirectional"))
    )
    (net (code "47") (name "Net-(U3-V3)") (class "Default")
      (node (ref "C17") (pin "1") (pinfunction "1_1") (pintype "passive"))
      (node (ref "U3") (pin "4") (pinfunction "V3_4") (pintype "bidirectional"))
    )
    (net (code "48") (name "PI-5V") (class "Default")
      (node (ref "C4") (pin "1") (pinfunction "1_1") (pintype "passive"))
      (node (ref "C8") (pin "1") (pinfunction "1_1") (pintype "passive"))
      (node (ref "JP4") (pin "1") (pinfunction "1_1") (pintype "passive"))
      (node (ref "Q10") (pin "4") (pinfunction "E_4") (pintype "passive"))
      (node (ref "Q12") (pin "3") (pinfunction "D_3") (pintype "bidirectional"))
      (node (ref "Q7") (pin "2") (pinfunction "S_2") (pintype "bidirectional"))
      (node (ref "Q8") (pin "4") (pinfunction "E_4") (pintype "passive"))
      (node (ref "Q9") (pin "2") (pinfunction "S_2") (pintype "bidirectional"))
      (node (ref "R1") (pin "2") (pinfunction "2_2") (pintype "passive"))
      (node (ref "R18") (pin "2") (pinfunction "2_2") (pintype "passive"))
      (node (ref "R19") (pin "2") (pinfunction "2_2") (pintype "passive"))
      (node (ref "R2") (pin "2") (pinfunction "2_2") (pintype "passive"))
      (node (ref "TP24") (pin "P$1") (pinfunction "1_P$1") (pintype "bidirectional"))
      (node (ref "U1") (pin "28") (pinfunction "VDD_28") (pintype "bidirectional"))
      (node (ref "U2") (pin "5") (pinfunction "P$V+_5") (pintype "bidirectional"))
    )
    (net (code "49") (name "PI-RXI") (class "Default")
      (node (ref "J1") (pin "10") (pinfunction "RXI_10") (pintype "input"))
      (node (ref "S1") (pin "2") (pinfunction "P_2") (pintype "passive"))
      (node (ref "TP26") (pin "P$1") (pinfunction "1_P$1") (pintype "bidirectional"))
    )
    (net (code "50") (name "PI-TXO") (class "Default")
      (node (ref "D2") (pin "C") (pinfunction "C_C") (pintype "passive"))
      (node (ref "J1") (pin "8") (pinfunction "TXO_8") (pintype "output"))
      (node (ref "J21") (pin "1") (pinfunction "1_1") (pintype "passive"))
      (node (ref "TP20") (pin "P$1") (pinfunction "1_P$1") (pintype "bidirectional"))
      (node (ref "U3") (pin "3") (pinfunction "RXI_3") (pintype "bidirectional"))
    )
    (net (code "51") (name "RVR-5V") (class "Default")
      (node (ref "J21") (pin "4") (pinfunction "4_4") (pintype "passive"))
      (node (ref "Q2") (pin "3") (pinfunction "D_3") (pintype "bidirectional"))
      (node (ref "Q3") (pin "1") (pinfunction "E_1") (pintype "passive"))
      (node (ref "Q7") (pin "3") (pinfunction "D_3") (pintype "bidirectional"))
      (node (ref "Q8") (pin "1") (pinfunction "E_1") (pintype "passive"))
      (node (ref "R20") (pin "2") (pinfunction "2_2") (pintype "passive"))
      (node (ref "TP25") (pin "P$1") (pinfunction "1_P$1") (pintype "bidirectional"))
      (node (ref "U2") (pin "1") (pinfunction "A_1") (pintype "bidirectional"))
    )
    (net (code "52") (name "RVR-TXO") (class "Default")
      (node (ref "J21") (pin "2") (pinfunction "2_2") (pintype "passive"))
      (node (ref "S1") (pin "3") (pinfunction "S_3") (pintype "passive"))
      (node (ref "TP21") (pin "P$1") (pinfunction "1_P$1") (pintype "bidirectional"))
    )
    (net (code "53") (name "SERVO") (class "Default")
      (node (ref "C5") (pin "+") (pinfunction "+_+") (pintype "passive"))
      (node (ref "C6") (pin "1") (pinfunction "1_1") (pintype "passive"))
      (node (ref "J10") (pin "2") (pinfunction "2_2") (pintype "passive"))
      (node (ref "J11") (pin "2") (pinfunction "2_2") (pintype "passive"))
      (node (ref "J12") (pin "2") (pinfunction "2_2") (pintype "passive"))
      (node (ref "J13") (pin "2") (pinfunction "2_2") (pintype "passive"))
      (node (ref "J14") (pin "2") (pinfunction "2_2") (pintype "passive"))
      (node (ref "J15") (pin "2") (pinfunction "2_2") (pintype "passive"))
      (node (ref "J16") (pin "2") (pinfunction "2_2") (pintype "passive"))
      (node (ref "J17") (pin "2") (pinfunction "2_2") (pintype "passive"))
      (node (ref "J18") (pin "2") (pinfunction "2_2") (pintype "passive"))
      (node (ref "J3") (pin "2") (pinfunction "2_2") (pintype "passive"))
      (node (ref "J4") (pin "2") (pinfunction "2_2") (pintype "passive"))
      (node (ref "J5") (pin "2") (pinfunction "2_2") (pintype "passive"))
      (node (ref "J6") (pin "2") (pinfunction "2_2") (pintype "passive"))
      (node (ref "J7") (pin "2") (pinfunction "2_2") (pintype "passive"))
      (node (ref "J8") (pin "2") (pinfunction "2_2") (pintype "passive"))
      (node (ref "J9") (pin "2") (pinfunction "2_2") (pintype "passive"))
      (node (ref "Q12") (pin "2") (pinfunction "S_2") (pintype "bidirectional"))
      (node (ref "Q2") (pin "2") (pinfunction "S_2") (pintype "bidirectional"))
      (node (ref "Q3") (pin "4") (pinfunction "E_4") (pintype "passive"))
      (node (ref "Q5") (pin "2") (pinfunction "S_2") (pintype "bidirectional"))
      (node (ref "Q6") (pin "4") (pinfunction "E_4") (pintype "passive"))
      (node (ref "TP16") (pin "P$1") (pinfunction "1_P$1") (pintype "bidirectional"))
    )
    (net (code "54") (name "SHLD") (class "Default")
      (node (ref "J20") (pin "SHLD1") (pinfunction "SHLD_SHLD1") (pintype "bidirectional"))
      (node (ref "J20") (pin "SHLD2") (pinfunction "SHLD_SHLD2") (pintype "bidirectional"))
      (node (ref "J20") (pin "SHLD3") (pinfunction "SHLD_SHLD3") (pintype "bidirectional"))
      (node (ref "J20") (pin "SHLD4") (pinfunction "SHLD_SHLD4") (pintype "bidirectional"))
      (node (ref "J20") (pin "SHLD5") (pinfunction "SHLD_SHLD5") (pintype "bidirectional"))
      (node (ref "J20") (pin "SHLD6") (pinfunction "SHLD_SHLD6") (pintype "bidirectional"))
      (node (ref "J20") (pin "SHLD7") (pinfunction "SHLD_SHLD7") (pintype "bidirectional"))
      (node (ref "J20") (pin "SHLD8") (pinfunction "SHLD_SHLD8") (pintype "bidirectional"))
    )
    (net (code "55") (name "USB-5V") (class "Default")
      (node (ref "F2") (pin "2") (pinfunction "2_2") (pintype "bidirectional"))
      (node (ref "JP2") (pin "2") (pinfunction "2_2") (pintype "passive"))
      (node (ref "Q10") (pin "1") (pinfunction "E_1") (pintype "passive"))
      (node (ref "Q5") (pin "3") (pinfunction "D_3") (pintype "bidirectional"))
      (node (ref "Q6") (pin "1") (pinfunction "E_1") (pintype "passive"))
      (node (ref "Q9") (pin "3") (pinfunction "D_3") (pintype "bidirectional"))
      (node (ref "R21") (pin "2") (pinfunction "2_2") (pintype "passive"))
      (node (ref "U2") (pin "2") (pinfunction "B_2") (pintype "bidirectional"))
    )
    (net (code "56") (name "unconnected-(J1-CE0-Pad24)") (class "Default")
      (node (ref "J1") (pin "24") (pinfunction "CE0_24") (pintype "output"))
    )
    (net (code "57") (name "unconnected-(J1-CE1-Pad26)") (class "Default")
      (node (ref "J1") (pin "26") (pinfunction "CE1_26") (pintype "output"))
    )
    (net (code "58") (name "unconnected-(J1-GP4-Pad7)") (class "Default")
      (node (ref "J1") (pin "7") (pinfunction "GP4_7") (pintype "bidirectional"))
    )
    (net (code "59") (name "unconnected-(J1-GP5-Pad29)") (class "Default")
      (node (ref "J1") (pin "29") (pinfunction "GP5_29") (pintype "bidirectional"))
    )
    (net (code "60") (name "unconnected-(J1-GP6-Pad31)") (class "Default")
      (node (ref "J1") (pin "31") (pinfunction "GP6_31") (pintype "bidirectional"))
    )
    (net (code "61") (name "unconnected-(J1-GP12-Pad32)") (class "Default")
      (node (ref "J1") (pin "32") (pinfunction "GP12_32") (pintype "bidirectional"))
    )
    (net (code "62") (name "unconnected-(J1-GP13-Pad33)") (class "Default")
      (node (ref "J1") (pin "33") (pinfunction "GP13_33") (pintype "bidirectional"))
    )
    (net (code "63") (name "unconnected-(J1-GP16-Pad36)") (class "Default")
      (node (ref "J1") (pin "36") (pinfunction "GP16_36") (pintype "bidirectional"))
    )
    (net (code "64") (name "unconnected-(J1-GP17-Pad11)") (class "Default")
      (node (ref "J1") (pin "11") (pinfunction "GP17_11") (pintype "bidirectional"))
    )
    (net (code "65") (name "unconnected-(J1-GP18#-Pad12)") (class "Default")
      (node (ref "J1") (pin "12") (pinfunction "GP18#_12") (pintype "bidirectional"))
    )
    (net (code "66") (name "unconnected-(J1-GP19-Pad35)") (class "Default")
      (node (ref "J1") (pin "35") (pinfunction "GP19_35") (pintype "bidirectional"))
    )
    (net (code "67") (name "unconnected-(J1-GP20-Pad38)") (class "Default")
      (node (ref "J1") (pin "38") (pinfunction "GP20_38") (pintype "bidirectional"))
    )
    (net (code "68") (name "unconnected-(J1-GP21-Pad40)") (class "Default")
      (node (ref "J1") (pin "40") (pinfunction "GP21_40") (pintype "bidirectional"))
    )
    (net (code "69") (name "unconnected-(J1-GP22-Pad15)") (class "Default")
      (node (ref "J1") (pin "15") (pinfunction "GP22_15") (pintype "bidirectional"))
    )
    (net (code "70") (name "unconnected-(J1-GP23-Pad16)") (class "Default")
      (node (ref "J1") (pin "16") (pinfunction "GP23_16") (pintype "bidirectional"))
    )
    (net (code "71") (name "unconnected-(J1-GP24-Pad18)") (class "Default")
      (node (ref "J1") (pin "18") (pinfunction "GP24_18") (pintype "bidirectional"))
    )
    (net (code "72") (name "unconnected-(J1-GP25-Pad22)") (class "Default")
      (node (ref "J1") (pin "22") (pinfunction "GP25_22") (pintype "bidirectional"))
    )
    (net (code "73") (name "unconnected-(J1-GP26-Pad37)") (class "Default")
      (node (ref "J1") (pin "37") (pinfunction "GP26_37") (pintype "bidirectional"))
    )
    (net (code "74") (name "unconnected-(J1-GP27-Pad13)") (class "Default")
      (node (ref "J1") (pin "13") (pinfunction "GP27_13") (pintype "bidirectional"))
    )
    (net (code "75") (name "unconnected-(J1-ID_SC-Pad28)") (class "Default")
      (node (ref "J1") (pin "28") (pinfunction "ID_SC_28") (pintype "bidirectional"))
    )
    (net (code "76") (name "unconnected-(J1-ID_SD-Pad27)") (class "Default")
      (node (ref "J1") (pin "27") (pinfunction "ID_SD_27") (pintype "bidirectional"))
    )
    (net (code "77") (name "unconnected-(J1-MISO-Pad21)") (class "Default")
      (node (ref "J1") (pin "21") (pinfunction "MISO_21") (pintype "input"))
    )
    (net (code "78") (name "unconnected-(J1-MOSI-Pad19)") (class "Default")
      (node (ref "J1") (pin "19") (pinfunction "MOSI_19") (pintype "output"))
    )
    (net (code "79") (name "unconnected-(J1-SCLK-Pad23)") (class "Default")
      (node (ref "J1") (pin "23") (pinfunction "SCLK_23") (pintype "output"))
    )
    (net (code "80") (name "unconnected-(U1-A0-Pad1)") (class "Default")
      (node (ref "U1") (pin "1") (pinfunction "A0_1") (pintype "bidirectional"))
    )
    (net (code "81") (name "unconnected-(U1-A1-Pad2)") (class "Default")
      (node (ref "U1") (pin "2") (pinfunction "A1_2") (pintype "bidirectional"))
    )
    (net (code "82") (name "unconnected-(U1-A2-Pad3)") (class "Default")
      (node (ref "U1") (pin "3") (pinfunction "A2_3") (pintype "bidirectional"))
    )
    (net (code "83") (name "unconnected-(U1-A3-Pad4)") (class "Default")
      (node (ref "U1") (pin "4") (pinfunction "A3_4") (pintype "bidirectional"))
    )
    (net (code "84") (name "unconnected-(U1-A4-Pad5)") (class "Default")
      (node (ref "U1") (pin "5") (pinfunction "A4_5") (pintype "bidirectional"))
    )
    (net (code "85") (name "unconnected-(U1-A5-Pad24)") (class "Default")
      (node (ref "U1") (pin "24") (pinfunction "A5_24") (pintype "bidirectional"))
    )
    (net (code "86") (name "unconnected-(U3-R232-Pad15)") (class "Default")
      (node (ref "U3") (pin "15") (pinfunction "R232_15") (pintype "bidirectional"))
    )
    (net (code "87") (name "unconnected-(U3-~{CTS}-Pad9)") (class "Default")
      (node (ref "U3") (pin "9") (pinfunction "~{CTS}_9") (pintype "bidirectional"))
    )
    (net (code "88") (name "unconnected-(U3-~{DCD}-Pad12)") (class "Default")
      (node (ref "U3") (pin "12") (pinfunction "~{DCD}_12") (pintype "bidirectional"))
    )
    (net (code "89") (name "unconnected-(U3-~{DSR}-Pad10)") (class "Default")
      (node (ref "U3") (pin "10") (pinfunction "~{DSR}_10") (pintype "bidirectional"))
    )
    (net (code "90") (name "unconnected-(U3-~{DTR}-Pad13)") (class "Default")
      (node (ref "U3") (pin "13") (pinfunction "~{DTR}_13") (pintype "bidirectional"))
    )
    (net (code "91") (name "unconnected-(U3-~{RI}-Pad11)") (class "Default")
      (node (ref "U3") (pin "11") (pinfunction "~{RI}_11") (pintype "bidirectional"))
    )
    (net (code "92") (name "unconnected-(U3-~{RTS}-Pad14)") (class "Default")
      (node (ref "U3") (pin "14") (pinfunction "~{RTS}_14") (pintype "bidirectional"))
    )
  )
)
